# Agilent_OCXO.net
KiCad netlist of a schematic drawn in Altium Designer
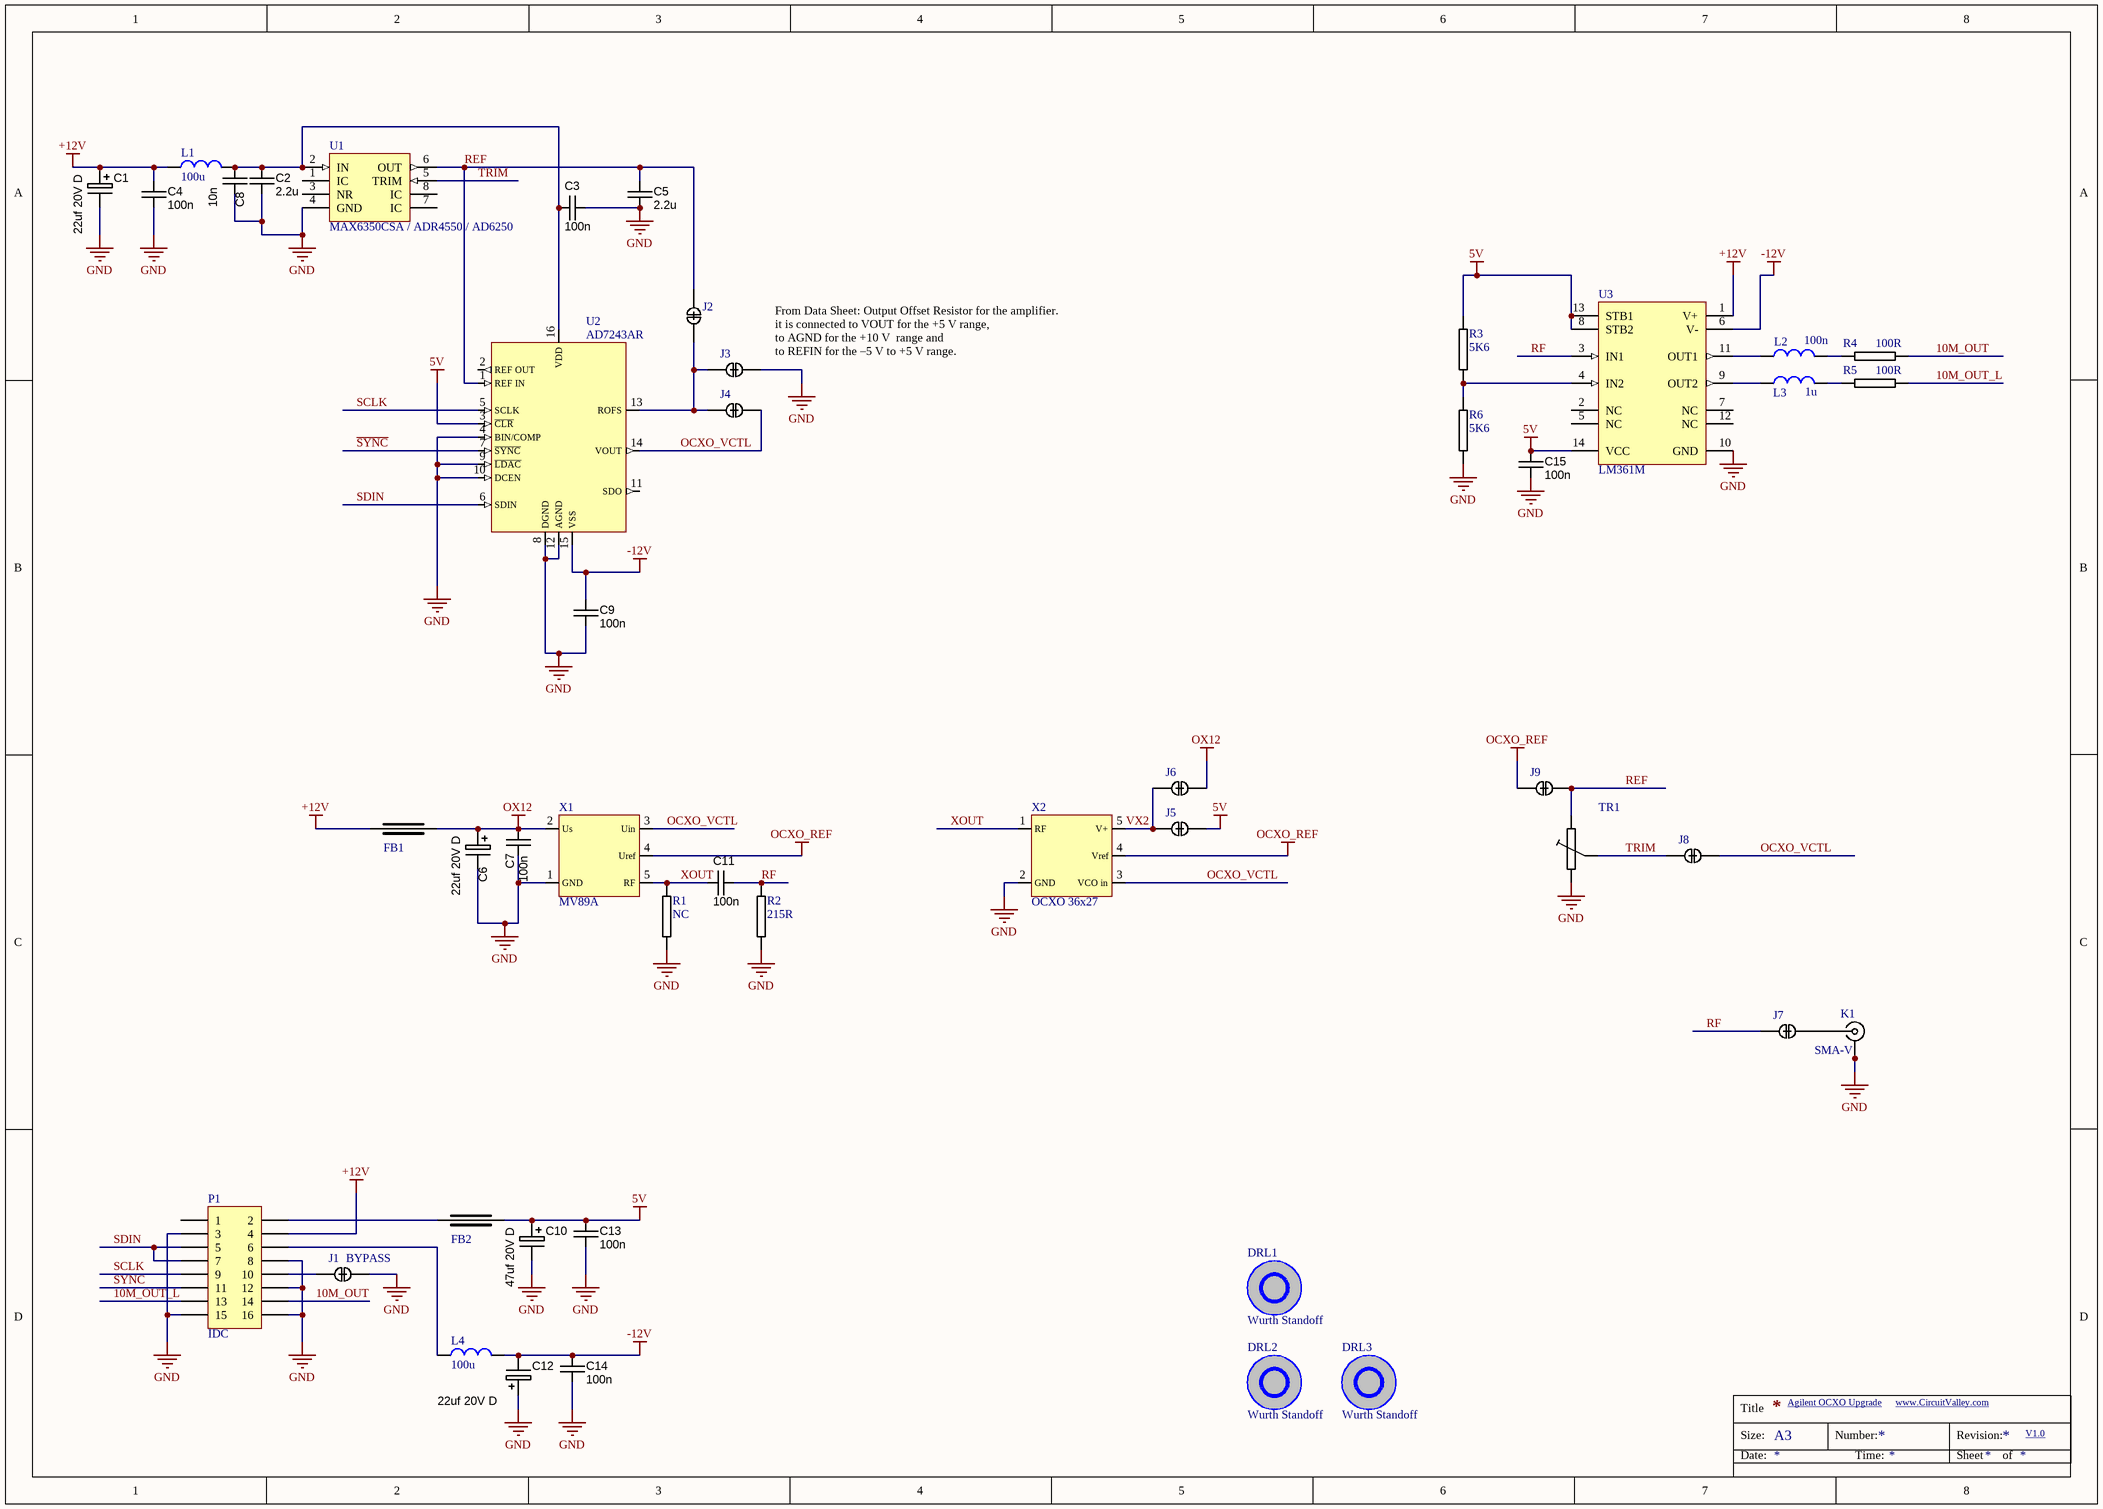
[diagram p0: Agilent_OCXO.SchDoc]

(export (version "E")
  (design (tool "Eeschema 10.0.6"))
  (components
    (comp (ref "C1")
      (value "22uf 20V D")
      (footprint "CAPMP7343X310N")
      (description "Capacitor SMD Tant 330uF 20% 6V3 2917")
      (fields
        (field (name "TOLERANCE") "±20%")
        (field (name "MANUFACTURER PART NUMBER") "T520D337M006ATE015")
      )
      (libsource (lib "PBL - Capacitors") (part "CAPT_330u_2917_6V3"))
    )
    (comp (ref "C2")
      (value "2.2u")
      (footprint "CAPC1608N")
      (description "Capacitor SMD Cer 10pF 5% 50V NP0 0603")
      (fields (field (name "TOLERANCE") "±5%") (field (name "PART") "GRM188R6YA225KA12D"))
      (libsource (lib "PBL - Capacitors") (part "CAPC_10p_0603_NP0_1%_50V"))
    )
    (comp (ref "C3")
      (value "100n")
      (footprint "CAPC1608N")
      (description "Capacitor SMD Cer 10pF 5% 50V NP0 0603")
      (fields (field (name "TOLERANCE") "±5%") (field (name "PART") "C0603X104K5RAC"))
      (libsource (lib "PBL - Capacitors") (part "CAPC_10p_0603_NP0_1%_50V"))
    )
    (comp (ref "C4")
      (value "100n")
      (footprint "CAPC1608N")
      (description "Capacitor SMD Cer 10pF 5% 50V NP0 0603")
      (fields (field (name "TOLERANCE") "±5%"))
      (libsource (lib "PBL - Capacitors") (part "CAPC_10p_0603_NP0_1%_50V"))
    )
    (comp (ref "C5")
      (value "2.2u")
      (footprint "CAPC1608N")
      (description "Capacitor SMD Cer 10pF 5% 50V NP0 0603")
      (fields (field (name "TOLERANCE") "±5%") (field (name "PART") "GRM188R6YA225KA12D"))
      (libsource (lib "PBL - Capacitors") (part "CAPC_10p_0603_NP0_1%_50V"))
    )
    (comp (ref "C6")
      (value "22uf 20V D")
      (footprint "CAPMP7343X310N")
      (description "Capacitor SMD Tant 330uF 20% 6V3 2917")
      (fields
        (field (name "TOLERANCE") "±20%")
        (field (name "MANUFACTURER PART NUMBER") "T520D337M006ATE015")
      )
      (libsource (lib "PBL - Capacitors") (part "CAPT_330u_2917_6V3"))
    )
    (comp (ref "C7")
      (value "100n")
      (footprint "CAPC1608N")
      (description "Capacitor SMD Cer 10pF 5% 50V NP0 0603")
      (fields (field (name "TOLERANCE") "±5%") (field (name "PART") "C0603X104K5RAC"))
      (libsource (lib "PBL - Capacitors") (part "CAPC_10p_0603_NP0_1%_50V"))
    )
    (comp (ref "C8")
      (value "10n")
      (footprint "CAPC1608N")
      (description "Capacitor SMD Cer 10pF 5% 50V NP0 0603")
      (fields (field (name "TOLERANCE") "±5%") (field (name "PART") "C0603X103K5RAC"))
      (libsource (lib "PBL - Capacitors") (part "CAPC_10p_0603_NP0_1%_50V"))
    )
    (comp (ref "C9")
      (value "100n")
      (footprint "CAPC1608N")
      (description "Capacitor SMD Cer 10pF 5% 50V NP0 0603")
      (fields (field (name "TOLERANCE") "±5%") (field (name "PART") "C0603X104K5RAC"))
      (libsource (lib "PBL - Capacitors") (part "CAPC_10p_0603_NP0_1%_50V"))
    )
    (comp (ref "C10")
      (value "47uf 20V D")
      (footprint "CAPMP7343X310N")
      (description "Capacitor SMD Tant 330uF 20% 6V3 2917")
      (fields
        (field (name "TOLERANCE") "±20%")
        (field (name "MANUFACTURER PART NUMBER") "T520D337M006ATE015")
      )
      (libsource (lib "PBL - Capacitors") (part "CAPT_330u_2917_6V3"))
    )
    (comp (ref "C11")
      (value "100n")
      (footprint "CAPC1608N")
      (description "Capacitor SMD Cer 10pF 5% 50V NP0 0603")
      (fields (field (name "TOLERANCE") "±5%") (field (name "PART") "C0603X104K5RAC"))
      (libsource (lib "PBL - Capacitors") (part "CAPC_10p_0603_NP0_1%_50V"))
    )
    (comp (ref "C12")
      (value "22uf 20V D")
      (footprint "CAPMP7343X310N")
      (description "Capacitor SMD Tant 330uF 20% 6V3 2917")
      (fields
        (field (name "TOLERANCE") "±20%")
        (field (name "MANUFACTURER PART NUMBER") "T520D337M006ATE015")
      )
      (libsource (lib "PBL - Capacitors") (part "CAPT_330u_2917_6V3"))
    )
    (comp (ref "C13")
      (value "100n")
      (footprint "CAPC1608N")
      (description "Capacitor SMD Cer 10pF 5% 50V NP0 0603")
      (fields (field (name "TOLERANCE") "±5%") (field (name "PART") "C0603X104K5RAC"))
      (libsource (lib "PBL - Capacitors") (part "CAPC_10p_0603_NP0_1%_50V"))
    )
    (comp (ref "C14")
      (value "100n")
      (footprint "CAPC1608N")
      (description "Capacitor SMD Cer 10pF 5% 50V NP0 0603")
      (fields (field (name "TOLERANCE") "±5%") (field (name "PART") "C0603X104K5RAC"))
      (libsource (lib "PBL - Capacitors") (part "CAPC_10p_0603_NP0_1%_50V"))
    )
    (comp (ref "C15")
      (value "100n")
      (footprint "CAPC1608N")
      (description "Capacitor SMD Cer 10pF 5% 50V NP0 0603")
      (fields (field (name "TOLERANCE") "±5%") (field (name "PART") "C0603X104K5RAC"))
      (libsource (lib "PBL - Capacitors") (part "CAPC_10p_0603_NP0_1%_50V"))
    )
    (comp (ref "DRL1")
      (value "Wurth Standoff")
      (footprint "Wurth_PCB_STANDOFF_7740_6mm")
      (fields (field (name "PART") "9774050360"))
      (libsource (lib "cvlib") (part "PCB_Sandoff"))
    )
    (comp (ref "DRL2")
      (value "Wurth Standoff")
      (footprint "Wurth_PCB_STANDOFF_7740_6mm")
      (fields (field (name "PART") "9774050360"))
      (libsource (lib "cvlib") (part "PCB_Sandoff"))
    )
    (comp (ref "DRL3")
      (value "Wurth Standoff")
      (footprint "Wurth_PCB_STANDOFF_7740_6mm")
      (fields (field (name "PART") "9774050360"))
      (libsource (lib "cvlib") (part "PCB_Sandoff"))
    )
    (comp (ref "FB1")
      (value "~")
      (footprint "0805FB-600Z")
      (description "FERRITE BEAD 600 OHM 2A")
      (fields (field (name "PART") "ILHB0805ER300V"))
      (libsource (lib "Generic") (part "0805FB-600Z"))
    )
    (comp (ref "FB2")
      (value "~")
      (footprint "0805FB-600Z")
      (description "FERRITE BEAD 600 OHM 2A")
      (fields (field (name "PART") "ILHB0805ER300V"))
      (libsource (lib "Generic") (part "0805FB-600Z"))
    )
    (comp (ref "J1")
      (value "BYPASS")
      (footprint "BYPASS-MINI-CLOSED")
      (description "SOLDERDOT BYPASS")
      (libsource (lib "Generic") (part "BYPASS-MINI-CLOSED"))
    )
    (comp (ref "J2")
      (value "~")
      (footprint "BYPASS-CLOSED")
      (description "SOLDERDOT BYPASS")
      (libsource (lib "Generic") (part "BYPASS-CLOSED"))
    )
    (comp (ref "J3")
      (value "~")
      (footprint "BYPASS-CLOSED")
      (description "SOLDERDOT BYPASS")
      (libsource (lib "Generic") (part "BYPASS-CLOSED"))
    )
    (comp (ref "J4")
      (value "~")
      (footprint "BYPASS-CLOSED")
      (description "SOLDERDOT BYPASS")
      (libsource (lib "Generic") (part "BYPASS-CLOSED"))
    )
    (comp (ref "J5")
      (value "~")
      (footprint "BYPASS-CLOSED")
      (description "SOLDERDOT BYPASS")
      (libsource (lib "Generic") (part "BYPASS-CLOSED"))
    )
    (comp (ref "J6")
      (value "~")
      (footprint "BYPASS-CLOSED")
      (description "SOLDERDOT BYPASS")
      (libsource (lib "Generic") (part "BYPASS-CLOSED"))
    )
    (comp (ref "J7")
      (value "~")
      (footprint "BYPASS-CLOSED")
      (description "SOLDERDOT BYPASS")
      (libsource (lib "Generic") (part "BYPASS-CLOSED"))
    )
    (comp (ref "J8")
      (value "~")
      (footprint "BYPASS-CLOSED")
      (description "SOLDERDOT BYPASS")
      (libsource (lib "Generic") (part "BYPASS-CLOSED"))
    )
    (comp (ref "J9")
      (value "~")
      (footprint "BYPASS-CLOSED")
      (description "SOLDERDOT BYPASS")
      (libsource (lib "Generic") (part "BYPASS-CLOSED"))
    )
    (comp (ref "K1")
      (value "SMA-V")
      (footprint "SMA-V")
      (description "SMA THREADED RF CONNECTOR VERTICAL")
      (fields (field (name "PART") "NC"))
      (libsource (lib "Generic") (part "SMA-V"))
    )
    (comp (ref "L1")
      (value "100u")
      (footprint "NLV32T")
      (fields (field (name "PART") "NLCV32T-101K-EF"))
      (libsource (lib "Inductor") (part "inductor_smd"))
    )
    (comp (ref "L2")
      (value "100n")
      (footprint "NLV32T")
      (fields (field (name "PART") "NLV32T-R10J-EF"))
      (libsource (lib "Inductor") (part "inductor_smd"))
    )
    (comp (ref "L3")
      (value "1u")
      (footprint "NLV32T")
      (fields (field (name "PART") "NLCV32T-1R0M-EF"))
      (libsource (lib "Inductor") (part "inductor_smd"))
    )
    (comp (ref "L4")
      (value "100u")
      (footprint "NLV32T")
      (fields (field (name "PART") "NLCV32T-101K-EF"))
      (libsource (lib "Inductor") (part "inductor_smd"))
    )
    (comp (ref "P1")
      (value "IDC")
      (footprint "HDR2X8")
      (description "Header, 8-Pin, Dual row")
      (fields (field (name "PART") "75869303LF") (field (name "PUBLISHER") "Altium Limited"))
      (libsource (lib "Miscellaneous Connectors") (part "Header 8X2"))
    )
    (comp (ref "R1")
      (value "NC")
      (footprint "0805R-5K6")
      (description "RESISTOR 0805 1/4 WATT THIN FILM")
      (libsource (lib "Generic") (part "0805R-5K6"))
    )
    (comp (ref "R2")
      (value "215R")
      (footprint "0805R-5K6")
      (description "RESISTOR 0805 1/4 WATT THIN FILM")
      (fields (field (name "PART") "RK73H2ATTD2150F"))
      (libsource (lib "Generic") (part "0805R-5K6"))
    )
    (comp (ref "R3")
      (value "5K6")
      (footprint "0805R-5K6")
      (description "RESISTOR 0805 1/4 WATT THIN FILM")
      (fields (field (name "PART") "RC0805FR-075K6L"))
      (libsource (lib "Generic") (part "0805R-5K6"))
    )
    (comp (ref "R4")
      (value "100R")
      (footprint "0805R-100")
      (description "RESISTOR 0805 1/4 WATT THIN FILM")
      (fields (field (name "PART") "RK73H2ATTE1000F"))
      (libsource (lib "Generic") (part "0805R-100"))
    )
    (comp (ref "R5")
      (value "100R")
      (footprint "0805R-100")
      (description "RESISTOR 0805 1/4 WATT THIN FILM")
      (fields (field (name "PART") "RK73H2ATTE1000F"))
      (libsource (lib "Generic") (part "0805R-100"))
    )
    (comp (ref "R6")
      (value "5K6")
      (footprint "0805R-5K6")
      (description "RESISTOR 0805 1/4 WATT THIN FILM")
      (fields (field (name "PART") "RC0805FR-075K6L"))
      (libsource (lib "Generic") (part "0805R-5K6"))
    )
    (comp (ref "TR1")
      (value "~")
      (footprint "TRIMMER-MT")
      (description "TRIMMABLE RESISTOR")
      (fields (field (name "PART") "T93XA103KT20"))
      (libsource (lib "Generic") (part "THTRIM-GENERIC"))
    )
    (comp (ref "U1")
      (value "MAX6350CSA / ADR4550 / AD6250")
      (footprint "NSO8_N")
      (description "1ppm/°C, Low-Noise, +5V Voltage Reference")
      (fields (field (name "PART") "MAX6350CSA") (field (name "PUBLISHER") "Altium Limited"))
      (libsource (lib "Maxim Power Mgt Voltage Reference") (part "MAX6350CSA"))
    )
    (comp (ref "U2") (value "AD7243AR") (footprint "SOIC-16_WIDE") (libsource (lib "cvlib") (part "AD7243")))
    (comp (ref "U3")
      (value "LM361M")
      (footprint "M14A_N")
      (description "High Speed Differential Comparator, 14-pin Narrow SOIC")
      (fields
        (field (name "MANUFACTURER") "National Semiconductor")
        (field (name "PUBLISHER") "Altium Limited")
      )
      (libsource (lib "NSC Amplifier") (part "LM361M"))
    )
    (comp (ref "X1") (value "MV89A") (footprint "MV89A") (libsource (lib "cvlib") (part "MV89A_OCXO")))
    (comp (ref "X2")
      (value "OCXO 36x27")
      (footprint "OCXO_Small")
      (fields (field (name "PART") "CTS 970"))
      (libsource (lib "cvlib") (part "OCXO_Small_Bliey_6891_isotemp_ocxo131"))
    )
  )
  (nets
    (net (code "1") (name "+12V") (class "Default")
      (node (ref "C1") (pin "1") (pintype "passive"))
      (node (ref "C4") (pin "2") (pintype "passive"))
      (node (ref "FB1") (pin "1") (pintype "passive"))
      (node (ref "L1") (pin "1") (pinfunction "1_1") (pintype "passive"))
      (node (ref "P1") (pin "4") (pinfunction "4_4") (pintype "passive"))
      (node (ref "U3") (pin "1") (pinfunction "V+_1") (pintype "power_in"))
    )
    (net (code "2") (name "-12V") (class "Default")
      (node (ref "C12") (pin "2") (pintype "passive"))
      (node (ref "C14") (pin "2") (pintype "passive"))
      (node (ref "C9") (pin "2") (pintype "passive"))
      (node (ref "L4") (pin "2") (pinfunction "2_2") (pintype "passive"))
      (node (ref "U2") (pin "15") (pinfunction "VSS_15") (pintype "power_in"))
      (node (ref "U3") (pin "6") (pinfunction "V-_6") (pintype "power_in"))
    )
    (net (code "3") (name "/10M_OUT") (class "Default")
      (node (ref "P1") (pin "14") (pinfunction "14_14") (pintype "passive"))
      (node (ref "R4") (pin "2") (pintype "passive"))
    )
    (net (code "4") (name "/10M_OUT_L") (class "Default")
      (node (ref "P1") (pin "13") (pinfunction "13_13") (pintype "passive"))
      (node (ref "R5") (pin "2") (pintype "passive"))
    )
    (net (code "5") (name "/OCXO_VCTL") (class "Default")
      (node (ref "J4") (pin "1") (pinfunction "1_1") (pintype "passive"))
      (node (ref "J8") (pin "1") (pinfunction "1_1") (pintype "passive"))
      (node (ref "U2") (pin "14") (pinfunction "VOUT_14") (pintype "output"))
      (node (ref "X1") (pin "3") (pinfunction "Uin_3") (pintype "passive"))
      (node (ref "X2") (pin "3") (pinfunction "VCO_in_3") (pintype "passive"))
    )
    (net (code "6") (name "/REF") (class "Default")
      (node (ref "C5") (pin "2") (pintype "passive"))
      (node (ref "J2") (pin "2") (pinfunction "2_2") (pintype "passive"))
      (node (ref "J9") (pin "1") (pinfunction "1_1") (pintype "passive"))
      (node (ref "TR1") (pin "2") (pinfunction "2_2") (pintype "passive"))
      (node (ref "U1") (pin "6") (pinfunction "OUT_6") (pintype "output"))
      (node (ref "U2") (pin "1") (pinfunction "REF_IN_1") (pintype "input"))
    )
    (net (code "7") (name "/RF") (class "Default")
      (node (ref "C11") (pin "1") (pintype "passive"))
      (node (ref "J7") (pin "2") (pinfunction "2_2") (pintype "passive"))
      (node (ref "R2") (pin "1") (pintype "passive"))
      (node (ref "U3") (pin "3") (pinfunction "IN1_3") (pintype "input"))
    )
    (net (code "8") (name "/SCLK") (class "Default")
      (node (ref "P1") (pin "9") (pinfunction "9_9") (pintype "passive"))
      (node (ref "U2") (pin "5") (pinfunction "SCLK_5") (pintype "input"))
    )
    (net (code "9") (name "/SDIN") (class "Default")
      (node (ref "P1") (pin "5") (pinfunction "5_5") (pintype "passive"))
      (node (ref "P1") (pin "7") (pinfunction "7_7") (pintype "passive"))
      (node (ref "U2") (pin "6") (pinfunction "SDIN_6") (pintype "input"))
    )
    (net (code "10") (name "/TRIM") (class "Default")
      (node (ref "J8") (pin "2") (pinfunction "2_2") (pintype "passive"))
      (node (ref "TR1") (pin "W") (pinfunction "W_W") (pintype "passive"))
      (node (ref "U1") (pin "5") (pinfunction "TRIM_5") (pintype "input"))
    )
    (net (code "11") (name "/VX2") (class "Default")
      (node (ref "J5") (pin "2") (pinfunction "2_2") (pintype "passive"))
      (node (ref "J6") (pin "2") (pinfunction "2_2") (pintype "passive"))
      (node (ref "X2") (pin "5") (pinfunction "V+_5") (pintype "passive"))
    )
    (net (code "12") (name "/XOUT") (class "Default")
      (node (ref "C11") (pin "2") (pintype "passive"))
      (node (ref "R1") (pin "1") (pintype "passive"))
      (node (ref "X1") (pin "5") (pinfunction "RF_5") (pintype "passive"))
      (node (ref "X2") (pin "1") (pinfunction "RF_1") (pintype "passive"))
    )
    (net (code "13") (name "/~{SYNC}") (class "Default")
      (node (ref "P1") (pin "11") (pinfunction "11_11") (pintype "passive"))
      (node (ref "U2") (pin "7") (pinfunction "~{SYNC}_7") (pintype "input"))
    )
    (net (code "14") (name "5V") (class "Default")
      (node (ref "C10") (pin "1") (pintype "passive"))
      (node (ref "C13") (pin "2") (pintype "passive"))
      (node (ref "C15") (pin "2") (pintype "passive"))
      (node (ref "FB2") (pin "2") (pintype "passive"))
      (node (ref "J5") (pin "1") (pinfunction "1_1") (pintype "passive"))
      (node (ref "R3") (pin "1") (pintype "passive"))
      (node (ref "U2") (pin "3") (pinfunction "~{CLR}_3") (pintype "input"))
      (node (ref "U3") (pin "13") (pinfunction "STB1_13") (pintype "power_in"))
      (node (ref "U3") (pin "14") (pinfunction "VCC_14") (pintype "power_in"))
      (node (ref "U3") (pin "8") (pinfunction "STB2_8") (pintype "power_in"))
    )
    (net (code "15") (name "GND") (class "Default")
      (node (ref "C1") (pin "2") (pintype "passive"))
      (node (ref "C10") (pin "2") (pintype "passive"))
      (node (ref "C12") (pin "1") (pintype "passive"))
      (node (ref "C13") (pin "1") (pintype "passive"))
      (node (ref "C14") (pin "1") (pintype "passive"))
      (node (ref "C15") (pin "1") (pintype "passive"))
      (node (ref "C2") (pin "1") (pintype "passive"))
      (node (ref "C3") (pin "2") (pintype "passive"))
      (node (ref "C4") (pin "1") (pintype "passive"))
      (node (ref "C5") (pin "1") (pintype "passive"))
      (node (ref "C6") (pin "2") (pintype "passive"))
      (node (ref "C7") (pin "1") (pintype "passive"))
      (node (ref "C8") (pin "1") (pintype "passive"))
      (node (ref "C9") (pin "1") (pintype "passive"))
      (node (ref "J1") (pin "2") (pinfunction "2_2") (pintype "passive"))
      (node (ref "J3") (pin "1") (pinfunction "1_1") (pintype "passive"))
      (node (ref "K1") (pin "2") (pinfunction "2_2") (pintype "passive"))
      (node (ref "K1") (pin "3") (pinfunction "3_3") (pintype "passive"))
      (node (ref "K1") (pin "4") (pinfunction "4_4") (pintype "passive"))
      (node (ref "K1") (pin "5") (pinfunction "5_5") (pintype "passive"))
      (node (ref "P1") (pin "12") (pinfunction "12_12") (pintype "passive"))
      (node (ref "P1") (pin "15") (pinfunction "15_15") (pintype "passive"))
      (node (ref "P1") (pin "16") (pinfunction "16_16") (pintype "passive"))
      (node (ref "P1") (pin "3") (pinfunction "3_3") (pintype "passive"))
      (node (ref "P1") (pin "8") (pinfunction "8_8") (pintype "passive"))
      (node (ref "R1") (pin "2") (pintype "passive"))
      (node (ref "R2") (pin "2") (pintype "passive"))
      (node (ref "R6") (pin "2") (pintype "passive"))
      (node (ref "TR1") (pin "1") (pinfunction "1_1") (pintype "passive"))
      (node (ref "U1") (pin "4") (pinfunction "GND_4") (pintype "power_in"))
      (node (ref "U2") (pin "10") (pinfunction "DCEN_10") (pintype "input"))
      (node (ref "U2") (pin "12") (pinfunction "AGND_12") (pintype "power_in"))
      (node (ref "U2") (pin "4") (pinfunction "BIN/COMP_4") (pintype "input"))
      (node (ref "U2") (pin "8") (pinfunction "DGND_8") (pintype "power_in"))
      (node (ref "U2") (pin "9") (pinfunction "~{LDAC}_9") (pintype "input"))
      (node (ref "U3") (pin "10") (pinfunction "GND_10") (pintype "power_in"))
      (node (ref "X1") (pin "1") (pinfunction "GND_1") (pintype "passive"))
      (node (ref "X2") (pin "2") (pinfunction "GND_2") (pintype "passive"))
    )
    (net (code "16") (name "Net-(FB2-Pad1)") (class "Default")
      (node (ref "FB2") (pin "1") (pintype "passive"))
      (node (ref "P1") (pin "2") (pinfunction "2_2") (pintype "passive"))
    )
    (net (code "17") (name "Net-(J1-Pad1)") (class "Default")
      (node (ref "J1") (pin "1") (pinfunction "1_1") (pintype "passive"))
      (node (ref "P1") (pin "10") (pinfunction "10_10") (pintype "passive"))
    )
    (net (code "18") (name "Net-(J7-Pad1)") (class "Default")
      (node (ref "J7") (pin "1") (pinfunction "1_1") (pintype "passive"))
      (node (ref "K1") (pin "1") (pinfunction "1_1") (pintype "passive"))
    )
    (net (code "19") (name "Net-(L2-Pad2)") (class "Default")
      (node (ref "L2") (pin "2") (pinfunction "2_2") (pintype "passive"))
      (node (ref "R4") (pin "1") (pintype "passive"))
    )
    (net (code "20") (name "Net-(L3-Pad2)") (class "Default")
      (node (ref "L3") (pin "2") (pinfunction "2_2") (pintype "passive"))
      (node (ref "R5") (pin "1") (pintype "passive"))
    )
    (net (code "21") (name "Net-(L4-Pad1)") (class "Default")
      (node (ref "L4") (pin "1") (pinfunction "1_1") (pintype "passive"))
      (node (ref "P1") (pin "6") (pinfunction "6_6") (pintype "passive"))
    )
    (net (code "22") (name "Net-(U1-IN)") (class "Default")
      (node (ref "C2") (pin "2") (pintype "passive"))
      (node (ref "C3") (pin "1") (pintype "passive"))
      (node (ref "C8") (pin "2") (pintype "passive"))
      (node (ref "L1") (pin "2") (pinfunction "2_2") (pintype "passive"))
      (node (ref "U1") (pin "2") (pinfunction "IN_2") (pintype "input"))
      (node (ref "U2") (pin "16") (pinfunction "VDD_16") (pintype "power_in"))
    )
    (net (code "23") (name "Net-(U2-ROFS)") (class "Default")
      (node (ref "J2") (pin "1") (pinfunction "1_1") (pintype "passive"))
      (node (ref "J3") (pin "2") (pinfunction "2_2") (pintype "passive"))
      (node (ref "J4") (pin "2") (pinfunction "2_2") (pintype "passive"))
      (node (ref "U2") (pin "13") (pinfunction "ROFS_13") (pintype "passive"))
    )
    (net (code "24") (name "Net-(U3-IN2)") (class "Default")
      (node (ref "R3") (pin "2") (pintype "passive"))
      (node (ref "R6") (pin "1") (pintype "passive"))
      (node (ref "U3") (pin "4") (pinfunction "IN2_4") (pintype "input"))
    )
    (net (code "25") (name "Net-(U3-OUT1)") (class "Default")
      (node (ref "L2") (pin "1") (pinfunction "1_1") (pintype "passive"))
      (node (ref "U3") (pin "11") (pinfunction "OUT1_11") (pintype "output"))
    )
    (net (code "26") (name "Net-(U3-OUT2)") (class "Default")
      (node (ref "L3") (pin "1") (pinfunction "1_1") (pintype "passive"))
      (node (ref "U3") (pin "9") (pinfunction "OUT2_9") (pintype "output"))
    )
    (net (code "27") (name "OCXO_REF") (class "Default")
      (node (ref "J9") (pin "2") (pinfunction "2_2") (pintype "passive"))
      (node (ref "X1") (pin "4") (pinfunction "Uref_4") (pintype "passive"))
      (node (ref "X2") (pin "4") (pinfunction "Vref_4") (pintype "passive"))
    )
    (net (code "28") (name "OX12") (class "Default")
      (node (ref "C6") (pin "1") (pintype "passive"))
      (node (ref "C7") (pin "2") (pintype "passive"))
      (node (ref "FB1") (pin "2") (pintype "passive"))
      (node (ref "J6") (pin "1") (pinfunction "1_1") (pintype "passive"))
      (node (ref "X1") (pin "2") (pinfunction "Us_2") (pintype "passive"))
    )
    (net (code "29") (name "unconnected-(P1-Pad1)") (class "Default")
      (node (ref "P1") (pin "1") (pinfunction "1_1") (pintype "passive"))
    )
    (net (code "30") (name "unconnected-(U1-IC-Pad1)") (class "Default")
      (node (ref "U1") (pin "1") (pinfunction "IC_1") (pintype "passive"))
    )
    (net (code "31") (name "unconnected-(U1-IC-Pad7)") (class "Default")
      (node (ref "U1") (pin "7") (pinfunction "IC_7") (pintype "passive"))
    )
    (net (code "32") (name "unconnected-(U1-IC-Pad8)") (class "Default")
      (node (ref "U1") (pin "8") (pinfunction "IC_8") (pintype "passive"))
    )
    (net (code "33") (name "unconnected-(U1-NR-Pad3)") (class "Default")
      (node (ref "U1") (pin "3") (pinfunction "NR_3") (pintype "passive"))
    )
    (net (code "34") (name "unconnected-(U2-REF_OUT-Pad2)") (class "Default")
      (node (ref "U2") (pin "2") (pinfunction "REF_OUT_2") (pintype "output"))
    )
    (net (code "35") (name "unconnected-(U2-SDO-Pad11)") (class "Default")
      (node (ref "U2") (pin "11") (pinfunction "SDO_11") (pintype "output"))
    )
    (net (code "36") (name "unconnected-(U3-NC-Pad2)") (class "Default")
      (node (ref "U3") (pin "2") (pinfunction "NC_2") (pintype "passive"))
    )
    (net (code "37") (name "unconnected-(U3-NC-Pad5)") (class "Default")
      (node (ref "U3") (pin "5") (pinfunction "NC_5") (pintype "passive"))
    )
    (net (code "38") (name "unconnected-(U3-NC-Pad7)") (class "Default")
      (node (ref "U3") (pin "7") (pinfunction "NC_7") (pintype "passive"))
    )
    (net (code "39") (name "unconnected-(U3-NC-Pad12)") (class "Default")
      (node (ref "U3") (pin "12") (pinfunction "NC_12") (pintype "passive"))
    )
  )
)
